# hackaday_com-ir-receiver-v1_4a.net
KiCad netlist of a schematic drawn in EAGLE
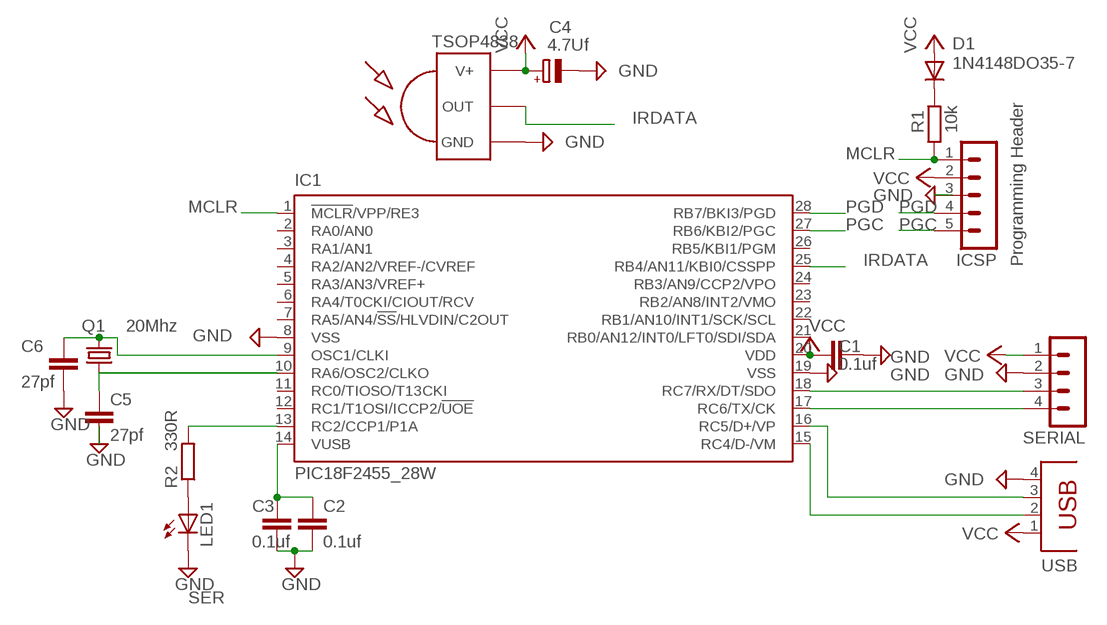
[diagram p0: schematic, sheet 1]

(export (version "E")
  (design (tool "Eeschema 10.0.6"))
  (components
    (comp (ref "C1")
      (value "0.1uf")
      (footprint "eagle-import:C025-024X044")
      (libsource (lib "eagle-import") (part "C-EU025-024X044"))
    )
    (comp (ref "C2")
      (value "0.1uf")
      (footprint "eagle-import:C025-024X044")
      (libsource (lib "eagle-import") (part "C-EU025-024X044"))
    )
    (comp (ref "C3")
      (value "0.1uf")
      (footprint "eagle-import:C025-024X044")
      (libsource (lib "eagle-import") (part "C-EU025-024X044"))
    )
    (comp (ref "C4")
      (value "4.7Uf")
      (footprint "eagle-import:E2,5-5")
      (libsource (lib "eagle-import") (part "CPOL-EUE2.5-5"))
    )
    (comp (ref "C5")
      (value "27pf")
      (footprint "eagle-import:C025-024X044")
      (libsource (lib "eagle-import") (part "C-EU025-024X044"))
    )
    (comp (ref "C6")
      (value "27pf")
      (footprint "eagle-import:C025-024X044")
      (libsource (lib "eagle-import") (part "C-EU025-024X044"))
    )
    (comp (ref "D1")
      (value "1N4148DO35-7")
      (footprint "eagle-import:DO35-7")
      (libsource (lib "eagle-import") (part "1N4148DO35-7"))
    )
    (comp (ref "IC1")
      (value "PIC18F2455_28W")
      (footprint "eagle-import:SO28W")
      (fields
        (field (name "MF") "MICROCHIP")
        (field (name "MPN") "PIC18F2455-I/SO")
        (field (name "MPN_1") "PIC18F2455-I/SO")
        (field (name "OC_FARNELL") "1579598")
        (field (name "OC_NEWARK") "64J3768")
      )
      (libsource (lib "eagle-import") (part "PIC18F2_28W455"))
    )
    (comp (ref "ICSP")
      (value "MA05-1")
      (footprint "eagle-import:MA05-1")
      (libsource (lib "eagle-import") (part "MA05-1"))
    )
    (comp (ref "LED1")
      (value "LED3MM")
      (footprint "eagle-import:LED3MM")
      (libsource (lib "eagle-import") (part "LED3MM"))
    )
    (comp (ref "Q1")
      (value "20Mhz")
      (footprint "eagle-import:HC49U-V")
      (libsource (lib "eagle-import") (part "CRYSTALHC49U-V"))
    )
    (comp (ref "R1")
      (value "10k")
      (footprint "eagle-import:0204V")
      (libsource (lib "eagle-import") (part "R-EU_0204/2V"))
    )
    (comp (ref "R2")
      (value "330R")
      (footprint "eagle-import:0204V")
      (libsource (lib "eagle-import") (part "R-EU_0204/2V"))
    )
    (comp (ref "SERIAL")
      (value "MA04-1")
      (footprint "eagle-import:MA04-1")
      (libsource (lib "eagle-import") (part "MA04-1"))
    )
    (comp (ref "TSOP-1738")
      (value "TSOP4838")
      (footprint "eagle-import:TSOP18XX")
      (libsource (lib "eagle-import") (part "TSOP4838"))
    )
    (comp (ref "USB")
      (value "PN61729")
      (footprint "eagle-import:PN61729")
      (libsource (lib "eagle-import") (part "PN61729"))
    )
  )
  (nets
    (net (code "1") (name "/IRDATA") (class "Default")
      (node (ref "IC1") (pin "25") (pinfunction "RB4/AN11/KBI0/CSSPP_25") (pintype "bidirectional"))
      (node (ref "TSOP-1738") (pin "OUT") (pinfunction "OUT_OUT") (pintype "bidirectional"))
    )
    (net (code "2") (name "/MCLR") (class "Default")
      (node (ref "IC1") (pin "1") (pinfunction "~{MCLR}/VPP/RE3_1") (pintype "input"))
      (node (ref "ICSP") (pin "1") (pinfunction "1_1") (pintype "passive"))
      (node (ref "R1") (pin "1") (pinfunction "1_1") (pintype "passive"))
    )
    (net (code "3") (name "/PGC") (class "Default")
      (node (ref "IC1") (pin "27") (pinfunction "RB6/KBI2/PGC_27") (pintype "bidirectional"))
      (node (ref "ICSP") (pin "5") (pinfunction "5_5") (pintype "passive"))
    )
    (net (code "4") (name "/PGD") (class "Default")
      (node (ref "IC1") (pin "28") (pinfunction "RB7/BKI3/PGD_28") (pintype "bidirectional"))
      (node (ref "ICSP") (pin "4") (pinfunction "4_4") (pintype "passive"))
    )
    (net (code "5") (name "GND") (class "Default")
      (node (ref "C1") (pin "2") (pinfunction "2_2") (pintype "passive"))
      (node (ref "C2") (pin "2") (pinfunction "2_2") (pintype "passive"))
      (node (ref "C3") (pin "2") (pinfunction "2_2") (pintype "passive"))
      (node (ref "C4") (pin "-") (pinfunction "-_-") (pintype "passive"))
      (node (ref "C5") (pin "2") (pinfunction "2_2") (pintype "passive"))
      (node (ref "C6") (pin "2") (pinfunction "2_2") (pintype "passive"))
      (node (ref "IC1") (pin "19") (pinfunction "VSS_19") (pintype "power_in"))
      (node (ref "IC1") (pin "8") (pinfunction "VSS_8") (pintype "power_in"))
      (node (ref "ICSP") (pin "3") (pinfunction "3_3") (pintype "passive"))
      (node (ref "LED1") (pin "K") (pinfunction "C_K") (pintype "passive"))
      (node (ref "SERIAL") (pin "2") (pinfunction "2_2") (pintype "passive"))
      (node (ref "TSOP-1738") (pin "GND") (pinfunction "GND_GND") (pintype "bidirectional"))
      (node (ref "USB") (pin "4") (pinfunction "4_4") (pintype "passive"))
    )
    (net (code "6") (name "Net-(D1-PadC)") (class "Default")
      (node (ref "D1") (pin "C") (pinfunction "C_C") (pintype "passive"))
      (node (ref "R1") (pin "2") (pinfunction "2_2") (pintype "passive"))
    )
    (net (code "7") (name "Net-(IC1-OSC1{slash}CLKI)") (class "Default")
      (node (ref "C6") (pin "1") (pinfunction "1_1") (pintype "passive"))
      (node (ref "IC1") (pin "9") (pinfunction "OSC1/CLKI_9") (pintype "input"))
      (node (ref "Q1") (pin "2") (pinfunction "2_2") (pintype "passive"))
    )
    (net (code "8") (name "Net-(IC1-RA6{slash}OSC2{slash}CLKO)") (class "Default")
      (node (ref "C5") (pin "1") (pinfunction "1_1") (pintype "passive"))
      (node (ref "IC1") (pin "10") (pinfunction "RA6/OSC2/CLKO_10") (pintype "output"))
      (node (ref "Q1") (pin "1") (pinfunction "1_1") (pintype "passive"))
    )
    (net (code "9") (name "Net-(IC1-RC2{slash}CCP1{slash}P1A)") (class "Default")
      (node (ref "IC1") (pin "13") (pinfunction "RC2/CCP1/P1A_13") (pintype "bidirectional"))
      (node (ref "R2") (pin "2") (pinfunction "2_2") (pintype "passive"))
    )
    (net (code "10") (name "Net-(IC1-RC4{slash}D-{slash}VM)") (class "Default")
      (node (ref "IC1") (pin "15") (pinfunction "RC4/D-/VM_15") (pintype "bidirectional"))
      (node (ref "USB") (pin "2") (pinfunction "2_2") (pintype "passive"))
    )
    (net (code "11") (name "Net-(IC1-RC5{slash}D+{slash}VP)") (class "Default")
      (node (ref "IC1") (pin "16") (pinfunction "RC5/D+/VP_16") (pintype "bidirectional"))
      (node (ref "USB") (pin "3") (pinfunction "3_3") (pintype "passive"))
    )
    (net (code "12") (name "Net-(IC1-RC6{slash}TX{slash}CK)") (class "Default")
      (node (ref "IC1") (pin "17") (pinfunction "RC6/TX/CK_17") (pintype "bidirectional"))
      (node (ref "SERIAL") (pin "4") (pinfunction "4_4") (pintype "passive"))
    )
    (net (code "13") (name "Net-(IC1-RC7{slash}RX{slash}DT{slash}SDO)") (class "Default")
      (node (ref "IC1") (pin "18") (pinfunction "RC7/RX/DT/SDO_18") (pintype "bidirectional"))
      (node (ref "SERIAL") (pin "3") (pinfunction "3_3") (pintype "passive"))
    )
    (net (code "14") (name "Net-(IC1-VUSB)") (class "Default")
      (node (ref "C2") (pin "1") (pinfunction "1_1") (pintype "passive"))
      (node (ref "C3") (pin "1") (pinfunction "1_1") (pintype "passive"))
      (node (ref "IC1") (pin "14") (pinfunction "VUSB_14") (pintype "bidirectional"))
    )
    (net (code "15") (name "Net-(LED1-PadA)") (class "Default")
      (node (ref "LED1") (pin "A") (pinfunction "A_A") (pintype "passive"))
      (node (ref "R2") (pin "1") (pinfunction "1_1") (pintype "passive"))
    )
    (net (code "16") (name "VCC") (class "Default")
      (node (ref "C1") (pin "1") (pinfunction "1_1") (pintype "passive"))
      (node (ref "C4") (pin "+") (pinfunction "+_+") (pintype "passive"))
      (node (ref "D1") (pin "A") (pinfunction "A_A") (pintype "passive"))
      (node (ref "IC1") (pin "20") (pinfunction "VDD_20") (pintype "power_in"))
      (node (ref "ICSP") (pin "2") (pinfunction "2_2") (pintype "passive"))
      (node (ref "SERIAL") (pin "1") (pinfunction "1_1") (pintype "passive"))
      (node (ref "TSOP-1738") (pin "VCC") (pinfunction "V+_VCC") (pintype "bidirectional"))
      (node (ref "USB") (pin "1") (pinfunction "1_1") (pintype "passive"))
    )
    (net (code "17") (name "unconnected-(IC1-RA0{slash}AN0-Pad2)") (class "Default")
      (node (ref "IC1") (pin "2") (pinfunction "RA0/AN0_2") (pintype "bidirectional"))
    )
    (net (code "18") (name "unconnected-(IC1-RA1{slash}AN1-Pad3)") (class "Default")
      (node (ref "IC1") (pin "3") (pinfunction "RA1/AN1_3") (pintype "bidirectional"))
    )
    (net (code "19") (name "unconnected-(IC1-RA2{slash}AN2{slash}VREF-{slash}CVREF-Pad4)") (class "Default")
      (node (ref "IC1") (pin "4") (pinfunction "RA2/AN2/VREF-/CVREF_4") (pintype "bidirectional"))
    )
    (net (code "20") (name "unconnected-(IC1-RA3{slash}AN3{slash}VREF+-Pad5)") (class "Default")
      (node (ref "IC1") (pin "5") (pinfunction "RA3/AN3/VREF+_5") (pintype "bidirectional"))
    )
    (net (code "21") (name "unconnected-(IC1-RA4{slash}T0CKI{slash}CIOUT{slash}RCV-Pad6)") (class "Default")
      (node (ref "IC1") (pin "6") (pinfunction "RA4/T0CKI/CIOUT/RCV_6") (pintype "bidirectional"))
    )
    (net (code "22") (name "unconnected-(IC1-RA5{slash}AN4{slash}~{SS}{slash}HLVDIN{slash}C2OUT-Pad7)") (class "Default")
      (node (ref "IC1") (pin "7") (pinfunction "RA5/AN4/~{SS}/HLVDIN/C2OUT_7") (pintype "bidirectional"))
    )
    (net (code "23") (name "unconnected-(IC1-RB0{slash}AN12{slash}INT0{slash}LFT0{slash}SDI{slash}SDA-Pad21)") (class "Default")
      (node (ref "IC1") (pin "21") (pinfunction "RB0/AN12/INT0/LFT0/SDI/SDA_21") (pintype "bidirectional"))
    )
    (net (code "24") (name "unconnected-(IC1-RB1{slash}AN10{slash}INT1{slash}SCK{slash}SCL-Pad22)") (class "Default")
      (node (ref "IC1") (pin "22") (pinfunction "RB1/AN10/INT1/SCK/SCL_22") (pintype "bidirectional"))
    )
    (net (code "25") (name "unconnected-(IC1-RB2{slash}AN8{slash}INT2{slash}VMO-Pad23)") (class "Default")
      (node (ref "IC1") (pin "23") (pinfunction "RB2/AN8/INT2/VMO_23") (pintype "bidirectional"))
    )
    (net (code "26") (name "unconnected-(IC1-RB3{slash}AN9{slash}CCP2{slash}VPO-Pad24)") (class "Default")
      (node (ref "IC1") (pin "24") (pinfunction "RB3/AN9/CCP2/VPO_24") (pintype "bidirectional"))
    )
    (net (code "27") (name "unconnected-(IC1-RB5{slash}KBI1{slash}PGM-Pad26)") (class "Default")
      (node (ref "IC1") (pin "26") (pinfunction "RB5/KBI1/PGM_26") (pintype "bidirectional"))
    )
    (net (code "28") (name "unconnected-(IC1-RC0{slash}TIOSO{slash}T13CKI-Pad11)") (class "Default")
      (node (ref "IC1") (pin "11") (pinfunction "RC0/TIOSO/T13CKI_11") (pintype "bidirectional"))
    )
    (net (code "29") (name "unconnected-(IC1-RC1{slash}T1OSI{slash}ICCP2{slash}~{UOE}-Pad12)") (class "Default")
      (node (ref "IC1") (pin "12") (pinfunction "RC1/T1OSI/ICCP2/~{UOE}_12") (pintype "bidirectional"))
    )
  )
)
